# Reference.net
KiCad netlist of a schematic drawn in Altium Designer
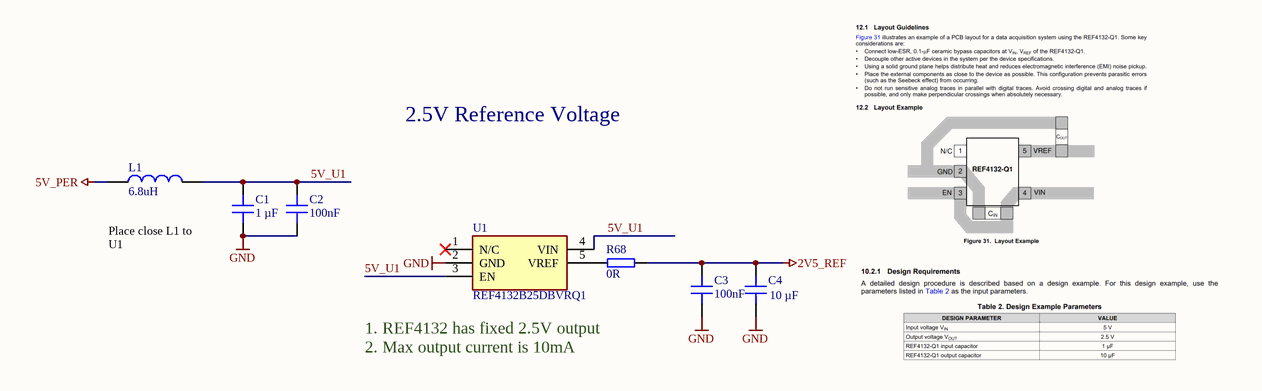
[diagram p0: Reference.SchDoc]

(export (version "E")
  (design (tool "Eeschema 10.0.6"))
  (components
    (comp (ref "C1")
      (value "1 µF")
      (footprint "C_0603")
      (description "50V 1uF X7R ±10% 0603 Multilayer Ceramic Capacitors MLCC - SMD/SMT ROHS")
      (fields
        (field (name "MANUFACTURER PART NUMBER") "UMK107AB7105KA-T")
        (field (name "MANUFACTURER") "Taiyo Yuden")
        (field (name "CREATED FROM") "NDiringer")
      )
      (libsource (lib "user") (part "Capacitor"))
    )
    (comp (ref "C2")
      (value "100nF")
      (footprint "C_0603")
      (description "50V 100nF X8R ±10% 0603")
      (fields
        (field (name "MANUFACTURER PART NUMBER") "CGA3E3X8R1H104KT0Y0N")
        (field (name "MANUFACTURER") "TDK")
        (field (name "CREATED FROM") "KIlhan")
      )
      (libsource (lib "user") (part "Capacitor"))
    )
    (comp (ref "C3")
      (value "100nF")
      (footprint "C_0603")
      (description "50V 100nF X8R ±10% 0603")
      (fields
        (field (name "MANUFACTURER PART NUMBER") "CGA3E3X8R1H104KT0Y0N")
        (field (name "MANUFACTURER") "TDK")
        (field (name "CREATED FROM") "KIlhan")
      )
      (libsource (lib "user") (part "Capacitor"))
    )
    (comp (ref "C4")
      (value "10 µF")
      (footprint "C_0805")
      (description "Capacitor 0805, 25 VDC, 10 µF, X5R")
      (fields
        (field (name "MANUFACTURER PART NUMBER") "GRM219R61E106KA12D")
        (field (name "MANUFACTURER") "muRata")
        (field (name "CREATED FROM") "MGremer")
      )
      (libsource (lib "user") (part "Capacitor"))
    )
    (comp (ref "L1")
      (value "6.8uH")
      (footprint "INDC1608X95N")
      (description "6.8uH ±10% 0603 Inductors (SMD) ROHS")
      (fields
        (field (name "MF") "EPCOS / TDK")
        (field (name "MPN") "B82464G4154M")
        (field (name "CREATED FROM") "KIlhan")
      )
      (libsource (lib "user") (part "B82464G4154M"))
    )
    (comp (ref "R68")
      (value "0R")
      (footprint "RES 0603_1608")
      (description "SMD resistor E24 series")
      (fields
        (field (name "MANUFACTURER PART NUMBER") "RC0603JR-070RL")
        (field (name "MANUFACTURER") "YAGEO")
        (field (name "CREATED FROM") "MGremer")
      )
      (libsource (lib "user") (part "Resistor"))
    )
    (comp (ref "U1")
      (value "REF4132B25DBVRQ1")
      (footprint "SOT95P280X145-5N")
      (description "Voltage Reference, 2.5V, ±0.05%, ±10mA")
      (fields
        (field (name "MANUFACTURER") "Texas Instruments")
        (field (name "LCSC PART NUMBER") "C2871658")
        (field (name "CREATED FROM") "DHufnagel")
      )
      (libsource (lib "user") (part "REF4132B25DBVRQ1"))
    )
  )
  (nets
    (net (code "1") (name "/5V_U1") (class "Default")
      (node (ref "C1") (pin "2") (pinfunction "2_2") (pintype "passive"))
      (node (ref "C2") (pin "2") (pinfunction "2_2") (pintype "passive"))
      (node (ref "L1") (pin "2") (pinfunction "2_2") (pintype "passive"))
      (node (ref "U1") (pin "3") (pinfunction "EN_3") (pintype "passive"))
      (node (ref "U1") (pin "4") (pinfunction "VIN_4") (pintype "passive"))
    )
    (net (code "2") (name "2V5_REF") (class "Default")
      (node (ref "C3") (pin "2") (pinfunction "2_2") (pintype "passive"))
      (node (ref "C4") (pin "2") (pinfunction "2_2") (pintype "passive"))
      (node (ref "R68") (pin "2") (pinfunction "2_2") (pintype "passive"))
    )
    (net (code "3") (name "5V_PER") (class "Default")
      (node (ref "L1") (pin "1") (pinfunction "1_1") (pintype "passive"))
    )
    (net (code "4") (name "GND") (class "Default")
      (node (ref "C1") (pin "1") (pinfunction "1_1") (pintype "passive"))
      (node (ref "C2") (pin "1") (pinfunction "1_1") (pintype "passive"))
      (node (ref "C3") (pin "1") (pinfunction "1_1") (pintype "passive"))
      (node (ref "C4") (pin "1") (pinfunction "1_1") (pintype "passive"))
      (node (ref "U1") (pin "2") (pinfunction "GND_2") (pintype "passive"))
    )
    (net (code "5") (name "Net-(U1-VREF)") (class "Default")
      (node (ref "R68") (pin "1") (pinfunction "1_1") (pintype "passive"))
      (node (ref "U1") (pin "5") (pinfunction "VREF_5") (pintype "passive"))
    )
    (net (code "6") (name "unconnected-(U1-N{slash}C-Pad1)") (class "Default")
      (node (ref "U1") (pin "1") (pinfunction "N/C_1") (pintype "passive+no_connect"))
    )
  )
)
